# Power.net
KiCad netlist of a schematic drawn in Altium Designer
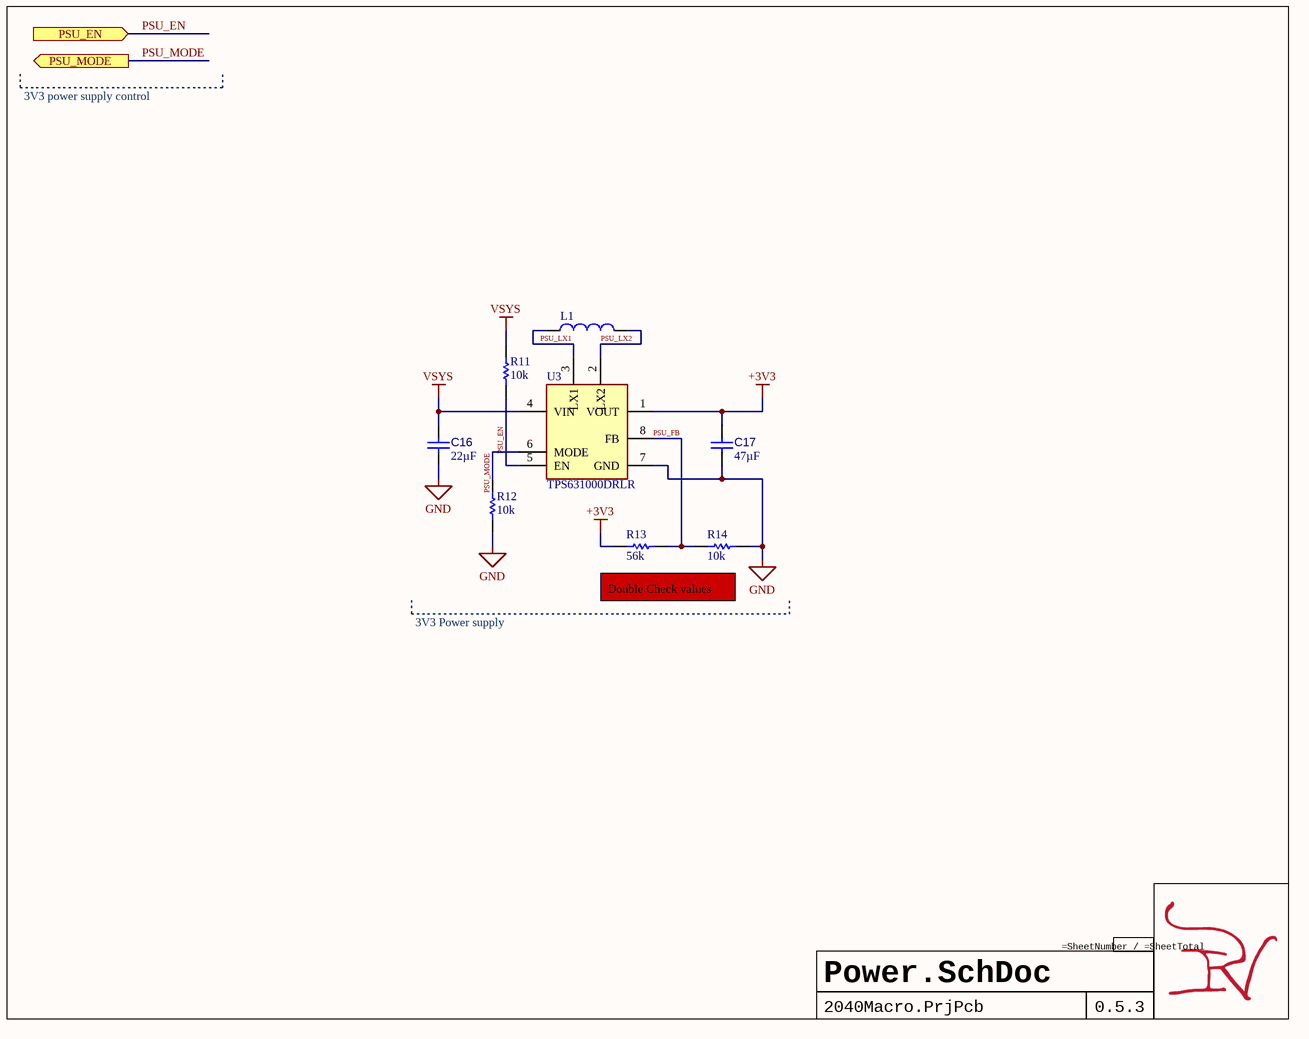
[diagram p0: Power.SchDoc]

(export (version "E")
  (design (tool "Eeschema 10.0.6"))
  (components
    (comp (ref "C16")
      (value "22µF")
      (footprint "CAP 0603_1608")
      (fields (field (name "Comment") "CL10A226KQ8NRNE"))
      (libsource (lib "IIT Motorsports") (part "CAP-NP-2"))
    )
    (comp (ref "C17")
      (value "47µF")
      (footprint "CAP 0805_2012")
      (fields (field (name "Comment") "CL21A476MQYNNNE"))
      (libsource (lib "IIT Motorsports") (part "CAP-NP-2"))
    )
    (comp (ref "L1")
      (value "CIGT252010EH1R0MNE")
      (footprint "FP-CIGT252010EH1R0MNE-MFG")
      (description "General Purpose Inductor, 1uH, 20%, 1 Element, Metal Composite-Core, SMD")
      (fields (field (name "TOLERANCE") "20%"))
      (libsource (lib "IIT Motorsports") (part "IND-2"))
    )
    (comp (ref "R11")
      (value "10k")
      (footprint "RES 0201_0603")
      (fields
        (field (name "POWER") "50mW")
        (field (name "TOLERANCE") "1%")
        (field (name "Comment") "10k-0201-0.05/1")
      )
      (libsource (lib "IIT Motorsports") (part "RES"))
    )
    (comp (ref "R12")
      (value "10k")
      (footprint "RES 0201_0603")
      (fields
        (field (name "POWER") "50mW")
        (field (name "TOLERANCE") "1%")
        (field (name "Comment") "10k-0201-0.05/1")
      )
      (libsource (lib "IIT Motorsports") (part "RES"))
    )
    (comp (ref "R13")
      (value "56k")
      (footprint "RES 0201_0603")
      (fields
        (field (name "TOLERANCE") "1%")
        (field (name "POWER") "50mW")
        (field (name "Comment") "56k-0204-0.05/1")
      )
      (libsource (lib "IIT Motorsports") (part "RES"))
    )
    (comp (ref "R14")
      (value "10k")
      (footprint "RES 0201_0603")
      (fields
        (field (name "POWER") "50mW")
        (field (name "TOLERANCE") "1%")
        (field (name "Comment") "10k-0201-0.05/1")
      )
      (libsource (lib "IIT Motorsports") (part "RES"))
    )
    (comp (ref "U3")
      (value "TPS631000DRLR")
      (footprint "SOTFL50P160X60-8N")
      (description "1.5-A output current, high power density buck-boost converter 8-SOT-5X3 -40 to 125")
      (fields (field (name "MOUSER PART NUMBER") "595-TPS631000DRLR"))
      (libsource (lib "IIT Motorsports") (part "TPS631000DRLR"))
    )
  )
  (nets
    (net (code "1") (name "+3V3") (class "Default")
      (node (ref "C17") (pin "2") (pinfunction "2_2") (pintype "passive"))
      (node (ref "R13") (pin "1") (pinfunction "1_1") (pintype "passive"))
      (node (ref "U3") (pin "1") (pinfunction "VOUT_1") (pintype "passive"))
    )
    (net (code "2") (name "/PSU_EN") (class "Default")
      (node (ref "R11") (pin "1") (pinfunction "1_1") (pintype "passive"))
      (node (ref "U3") (pin "5") (pinfunction "EN_5") (pintype "passive"))
    )
    (net (code "3") (name "/PSU_FB") (class "Default")
      (node (ref "R13") (pin "2") (pinfunction "2_2") (pintype "passive"))
      (node (ref "R14") (pin "1") (pinfunction "1_1") (pintype "passive"))
      (node (ref "U3") (pin "8") (pinfunction "FB_8") (pintype "passive"))
    )
    (net (code "4") (name "/PSU_LX1") (class "Default")
      (node (ref "L1") (pin "1") (pinfunction "1_1") (pintype "passive"))
      (node (ref "U3") (pin "3") (pinfunction "LX1_3") (pintype "passive"))
    )
    (net (code "5") (name "/PSU_LX2") (class "Default")
      (node (ref "L1") (pin "2") (pinfunction "2_2") (pintype "passive"))
      (node (ref "U3") (pin "2") (pinfunction "LX2_2") (pintype "passive"))
    )
    (net (code "6") (name "/PSU_MODE") (class "Default")
      (node (ref "R12") (pin "1") (pinfunction "1_1") (pintype "passive"))
      (node (ref "U3") (pin "6") (pinfunction "MODE_6") (pintype "passive"))
    )
    (net (code "7") (name "GND") (class "Default")
      (node (ref "C16") (pin "1") (pinfunction "1_1") (pintype "passive"))
      (node (ref "C17") (pin "1") (pinfunction "1_1") (pintype "passive"))
      (node (ref "R12") (pin "2") (pinfunction "2_2") (pintype "passive"))
      (node (ref "R14") (pin "2") (pinfunction "2_2") (pintype "passive"))
      (node (ref "U3") (pin "7") (pinfunction "GND_7") (pintype "passive"))
    )
    (net (code "8") (name "VSYS") (class "Default")
      (node (ref "C16") (pin "2") (pinfunction "2_2") (pintype "passive"))
      (node (ref "R11") (pin "2") (pinfunction "2_2") (pintype "passive"))
      (node (ref "U3") (pin "4") (pinfunction "VIN_4") (pintype "passive"))
    )
  )
)
